# Battery_Monitor_5.net
KiCad netlist of a schematic drawn in EAGLE
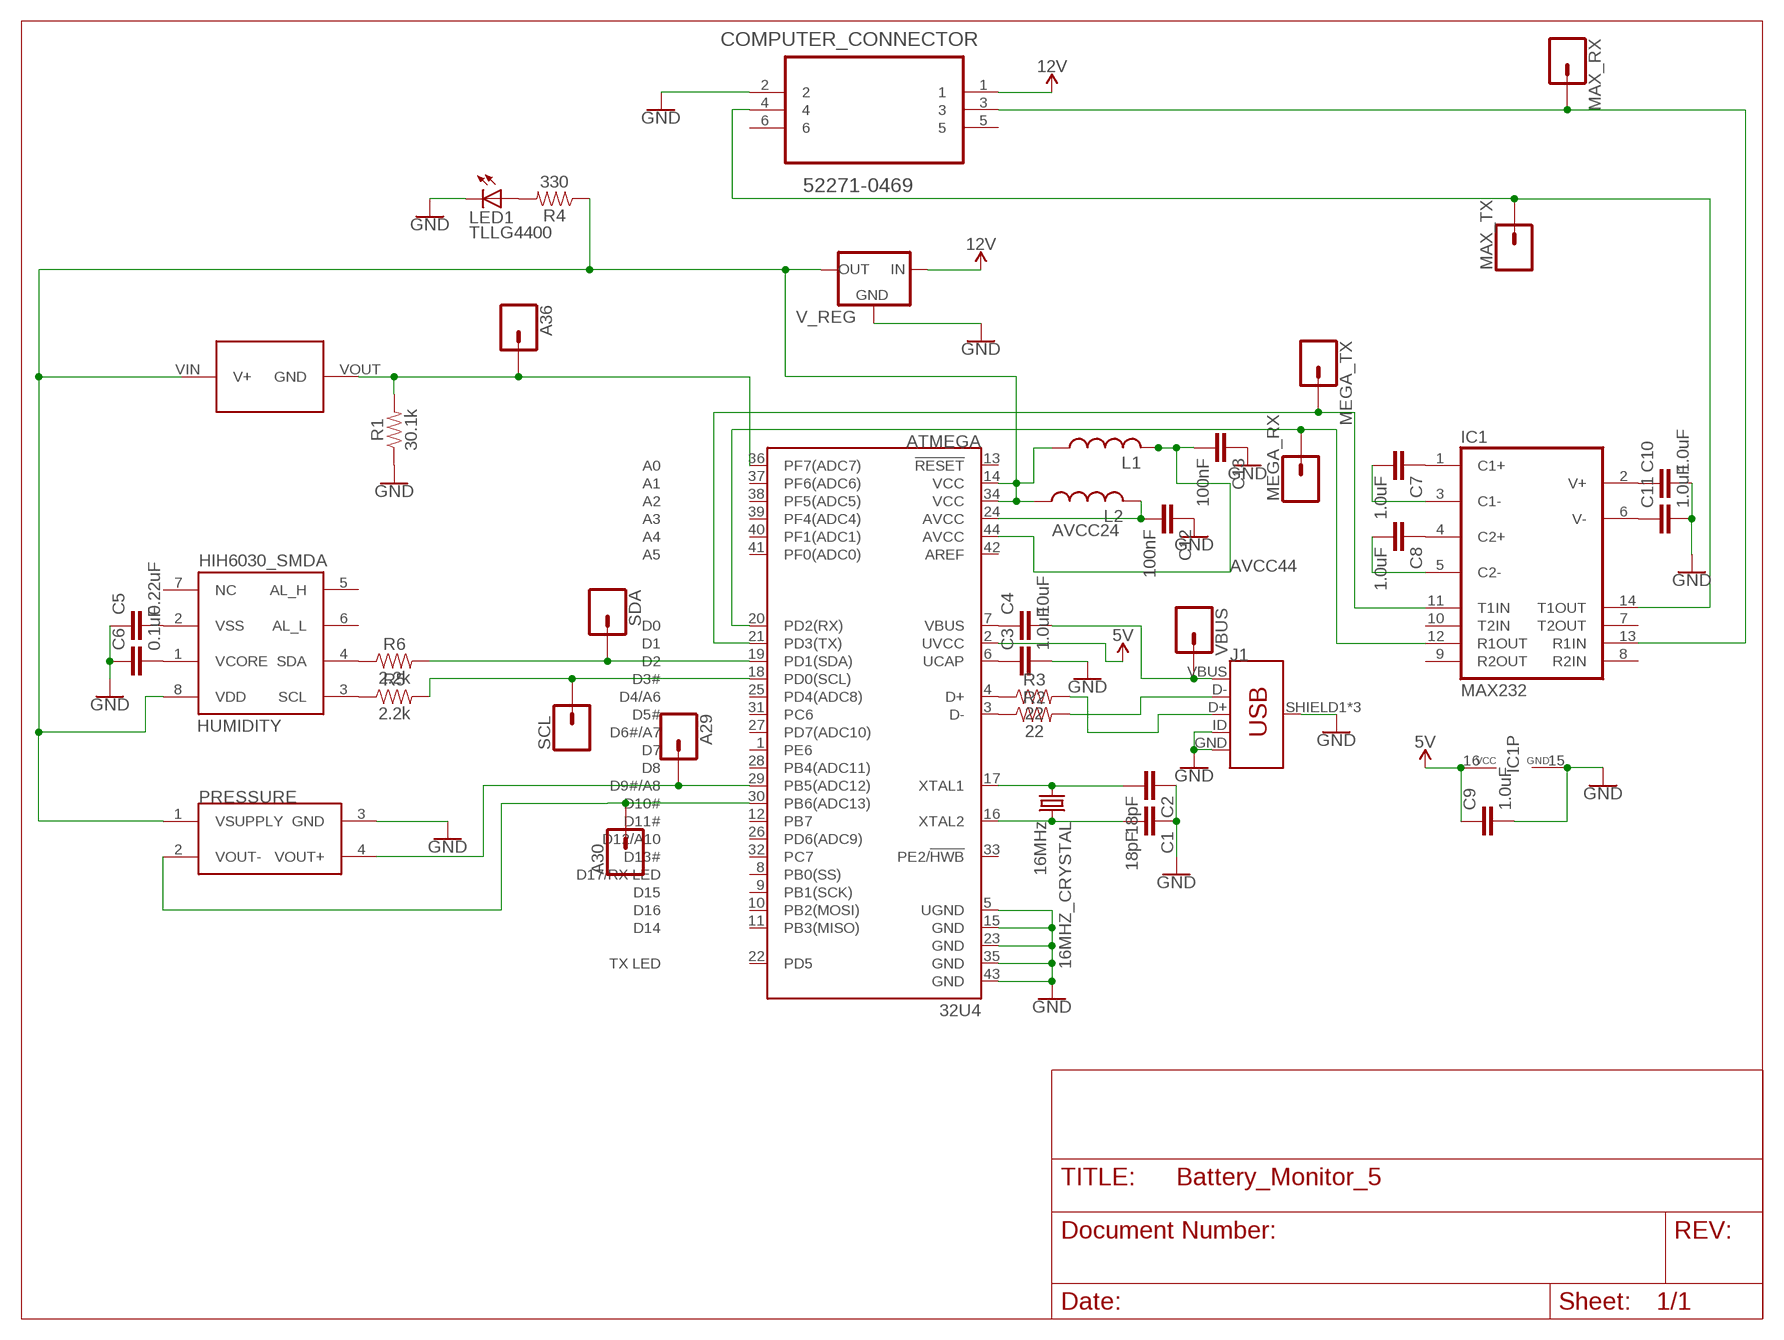
[diagram p0: schematic, sheet 1]

(export (version "E")
  (design (tool "Eeschema 10.0.6"))
  (components
    (comp (ref "16MHZ_CRYSTAL")
      (value "16MHz")
      (footprint "eagle-import:HC49_S")
      (libsource (lib "eagle-import") (part "CRYSTALHC49S"))
    )
    (comp (ref "A29")
      (value "CONN_01POGOPIN_HOLE_LARGE")
      (footprint "eagle-import:1X01_POGOPIN_HOLE_0.061_DIA")
      (libsource (lib "eagle-import") (part "CONN_01POGOPIN_HOLE_LARGE"))
    )
    (comp (ref "A30")
      (value "CONN_01POGOPIN_HOLE_LARGE")
      (footprint "eagle-import:1X01_POGOPIN_HOLE_0.061_DIA")
      (libsource (lib "eagle-import") (part "CONN_01POGOPIN_HOLE_LARGE"))
    )
    (comp (ref "A36")
      (value "CONN_01POGOPIN_HOLE_LARGE")
      (footprint "eagle-import:1X01_POGOPIN_HOLE_0.061_DIA")
      (libsource (lib "eagle-import") (part "CONN_01POGOPIN_HOLE_LARGE"))
    )
    (comp (ref "ATMEGA")
      (value "32U4")
      (footprint "eagle-import:QFN-44")
      (libsource (lib "eagle-import") (part "ATMEGA32U4QFN"))
    )
    (comp (ref "C1")
      (value "18pF")
      (footprint "eagle-import:0603")
      (libsource (lib "eagle-import") (part "18PF-0603-50V-5%"))
    )
    (comp (ref "C2")
      (value "18pF")
      (footprint "eagle-import:0603")
      (libsource (lib "eagle-import") (part "18PF-0603-50V-5%"))
    )
    (comp (ref "C3")
      (value "1.0uF")
      (footprint "eagle-import:0402")
      (libsource (lib "eagle-import") (part "1.0UF-0402-16V-10%"))
    )
    (comp (ref "C4")
      (value "10uF")
      (footprint "eagle-import:0603")
      (libsource (lib "eagle-import") (part "10UF-0603-6.3V-20%"))
    )
    (comp (ref "C5")
      (value "0.22uF")
      (footprint "eagle-import:0603")
      (libsource (lib "eagle-import") (part "0.22UF-0603-25V-10%"))
    )
    (comp (ref "C6")
      (value "0.1uF")
      (footprint "eagle-import:0402")
      (libsource (lib "eagle-import") (part "0.1UF-0402-16V-10%"))
    )
    (comp (ref "C7")
      (value "1.0uF")
      (footprint "eagle-import:0402")
      (libsource (lib "eagle-import") (part "1.0UF-0402-16V-10%"))
    )
    (comp (ref "C8")
      (value "1.0uF")
      (footprint "eagle-import:0402")
      (libsource (lib "eagle-import") (part "1.0UF-0402-16V-10%"))
    )
    (comp (ref "C9")
      (value "1.0uF")
      (footprint "eagle-import:0402")
      (libsource (lib "eagle-import") (part "1.0UF-0402-16V-10%"))
    )
    (comp (ref "C10")
      (value "1.0uF")
      (footprint "eagle-import:0402")
      (libsource (lib "eagle-import") (part "1.0UF-0402-16V-10%"))
    )
    (comp (ref "C11")
      (value "1.0uF")
      (footprint "eagle-import:0402")
      (libsource (lib "eagle-import") (part "1.0UF-0402-16V-10%"))
    )
    (comp (ref "C12")
      (value "100nF")
      (footprint "eagle-import:0402")
      (libsource (lib "eagle-import") (part "1.0UF-0402-16V-10%"))
    )
    (comp (ref "C13")
      (value "100nF")
      (footprint "eagle-import:0402")
      (libsource (lib "eagle-import") (part "1.0UF-0402-16V-10%"))
    )
    (comp (ref "COMPUTER_CONNECTOR")
      (value "52271-0469")
      (footprint "eagle-import:MOLEX_52271-0469")
      (libsource (lib "eagle-import") (part "52271-0469"))
    )
    (comp (ref "FLEX_SQ")
      (value "MOLEX_2WIRE2018")
      (footprint "eagle-import:SMT_MOLEX_PKG")
      (libsource (lib "eagle-import") (part "MOLEX_2WIRE2018"))
    )
    (comp (ref "HUMIDITY")
      (value "HIH6030_SMDA")
      (footprint "eagle-import:SMD-8")
      (libsource (lib "eagle-import") (part "HIH6030_SMDA"))
    )
    (comp (ref "IC1")
      (value "MAX232")
      (footprint "eagle-import:DIL16")
      (fields (field (name "MF") "MAXIM") (field (name "MPN") "MAX232ACPE+"))
      (libsource (lib "eagle-import") (part "MAX232"))
    )
    (comp (ref "J1")
      (value "USB_MICRO-B_FEMALE-SMT")
      (footprint "eagle-import:USB-B-MICRO-SMD")
      (libsource (lib "eagle-import") (part "USB_MICRO-B_FEMALE-SMT"))
    )
    (comp (ref "L1")
      (value "L-USL1812")
      (footprint "eagle-import:L1812")
      (libsource (lib "eagle-import") (part "L-USL1812"))
    )
    (comp (ref "L2")
      (value "L-USL1812")
      (footprint "eagle-import:L1812")
      (libsource (lib "eagle-import") (part "L-USL1812"))
    )
    (comp (ref "LED1")
      (value "TLLG4400")
      (footprint "eagle-import:LED3MM")
      (fields (field (name "MF") "VISHAY SEMICONDUCTOR"))
      (libsource (lib "eagle-import") (part "TLLG4400"))
    )
    (comp (ref "MAX_RX")
      (value "CONN_01POGOPIN_HOLE_LARGE")
      (footprint "eagle-import:1X01_POGOPIN_HOLE_0.061_DIA")
      (libsource (lib "eagle-import") (part "CONN_01POGOPIN_HOLE_LARGE"))
    )
    (comp (ref "MAX_TX")
      (value "CONN_01POGOPIN_HOLE_LARGE")
      (footprint "eagle-import:1X01_POGOPIN_HOLE_0.061_DIA")
      (libsource (lib "eagle-import") (part "CONN_01POGOPIN_HOLE_LARGE"))
    )
    (comp (ref "MEGA_RX")
      (value "CONN_01POGOPIN_HOLE_LARGE")
      (footprint "eagle-import:1X01_POGOPIN_HOLE_0.061_DIA")
      (libsource (lib "eagle-import") (part "CONN_01POGOPIN_HOLE_LARGE"))
    )
    (comp (ref "MEGA_TX")
      (value "CONN_01POGOPIN_HOLE_LARGE")
      (footprint "eagle-import:1X01_POGOPIN_HOLE_0.061_DIA")
      (libsource (lib "eagle-import") (part "CONN_01POGOPIN_HOLE_LARGE"))
    )
    (comp (ref "PRESSURE")
      (value "HONEYWELL_PRESSURE_SENSOR2018")
      (footprint "eagle-import:4PIN_SMT")
      (libsource (lib "eagle-import") (part "HONEYWELL_PRESSURE_SENSOR2018"))
    )
    (comp (ref "R1")
      (value "30.1k")
      (footprint "eagle-import:0603")
      (libsource (lib "eagle-import") (part "30.1KOHM-0603-1/10W-1%"))
    )
    (comp (ref "R2")
      (value "22")
      (footprint "eagle-import:0402")
      (libsource (lib "eagle-import") (part "22OHM-0402-1/10W-1%"))
    )
    (comp (ref "R3")
      (value "22")
      (footprint "eagle-import:0402")
      (libsource (lib "eagle-import") (part "22OHM-0402-1/10W-1%"))
    )
    (comp (ref "R4")
      (value "330")
      (footprint "eagle-import:0603")
      (libsource (lib "eagle-import") (part "330OHM-0603-1/10W-1%"))
    )
    (comp (ref "R5")
      (value "2.2k")
      (footprint "eagle-import:0603")
      (libsource (lib "eagle-import") (part "2.2KOHM-0603-1/10W-1%"))
    )
    (comp (ref "R6")
      (value "2.2k")
      (footprint "eagle-import:0603")
      (libsource (lib "eagle-import") (part "2.2KOHM-0603-1/10W-1%"))
    )
    (comp (ref "SCL")
      (value "CONN_01POGOPIN_HOLE_LARGE")
      (footprint "eagle-import:1X01_POGOPIN_HOLE_0.061_DIA")
      (libsource (lib "eagle-import") (part "CONN_01POGOPIN_HOLE_LARGE"))
    )
    (comp (ref "SDA")
      (value "CONN_01POGOPIN_HOLE_LARGE")
      (footprint "eagle-import:1X01_POGOPIN_HOLE_0.061_DIA")
      (libsource (lib "eagle-import") (part "CONN_01POGOPIN_HOLE_LARGE"))
    )
    (comp (ref "VBUS")
      (value "CONN_01POGOPIN_HOLE_LARGE")
      (footprint "eagle-import:1X01_POGOPIN_HOLE_0.061_DIA")
      (libsource (lib "eagle-import") (part "CONN_01POGOPIN_HOLE_LARGE"))
    )
    (comp (ref "V_REG")
      (value "DC_DC_78XXA")
      (footprint "eagle-import:DC-DC_CONVERTER_78XX")
      (libsource (lib "eagle-import") (part "DC_DC_78XXA"))
    )
  )
  (nets
    (net (code "1") (name "/AVCC24") (class "Default")
      (node (ref "ATMEGA") (pin "24") (pinfunction "AVCC_24") (pintype "bidirectional"))
      (node (ref "C12") (pin "2") (pinfunction "2_2") (pintype "passive"))
      (node (ref "L2") (pin "2") (pinfunction "2_2") (pintype "passive"))
    )
    (net (code "2") (name "/AVCC44") (class "Default")
      (node (ref "ATMEGA") (pin "44") (pinfunction "AVCC_44") (pintype "bidirectional"))
      (node (ref "C13") (pin "2") (pinfunction "2_2") (pintype "passive"))
      (node (ref "L1") (pin "2") (pinfunction "2_2") (pintype "passive"))
    )
    (net (code "3") (name "5V") (class "Default")
      (node (ref "ATMEGA") (pin "14") (pinfunction "VCC_14") (pintype "bidirectional"))
      (node (ref "ATMEGA") (pin "2") (pinfunction "UVCC_2") (pintype "bidirectional"))
      (node (ref "ATMEGA") (pin "34") (pinfunction "VCC_34") (pintype "bidirectional"))
      (node (ref "C9") (pin "1") (pinfunction "1_1") (pintype "passive"))
      (node (ref "FLEX_SQ") (pin "VIN") (pinfunction "V+_VIN") (pintype "bidirectional"))
      (node (ref "HUMIDITY") (pin "8") (pinfunction "VDD_8") (pintype "bidirectional"))
      (node (ref "IC1") (pin "16") (pinfunction "VCC_16") (pintype "power_in"))
      (node (ref "L1") (pin "1") (pinfunction "1_1") (pintype "passive"))
      (node (ref "L2") (pin "1") (pinfunction "1_1") (pintype "passive"))
      (node (ref "PRESSURE") (pin "1") (pinfunction "VSUPPLY_1") (pintype "bidirectional"))
      (node (ref "R4") (pin "1") (pinfunction "1_1") (pintype "passive"))
      (node (ref "V_REG") (pin "VOUT") (pinfunction "OUT_VOUT") (pintype "passive"))
    )
    (net (code "4") (name "12V") (class "Default")
      (node (ref "COMPUTER_CONNECTOR") (pin "1") (pinfunction "1_1") (pintype "passive"))
      (node (ref "V_REG") (pin "VIN") (pinfunction "IN_VIN") (pintype "input"))
    )
    (net (code "5") (name "GND") (class "Default")
      (node (ref "ATMEGA") (pin "15") (pinfunction "GND_15") (pintype "bidirectional"))
      (node (ref "ATMEGA") (pin "23") (pinfunction "GND_23") (pintype "bidirectional"))
      (node (ref "ATMEGA") (pin "35") (pinfunction "GND_35") (pintype "bidirectional"))
      (node (ref "ATMEGA") (pin "43") (pinfunction "GND_43") (pintype "bidirectional"))
      (node (ref "ATMEGA") (pin "5") (pinfunction "UGND_5") (pintype "bidirectional"))
      (node (ref "C1") (pin "1") (pinfunction "1_1") (pintype "passive"))
      (node (ref "C10") (pin "2") (pinfunction "2_2") (pintype "passive"))
      (node (ref "C11") (pin "2") (pinfunction "2_2") (pintype "passive"))
      (node (ref "C12") (pin "1") (pinfunction "1_1") (pintype "passive"))
      (node (ref "C13") (pin "1") (pinfunction "1_1") (pintype "passive"))
      (node (ref "C2") (pin "1") (pinfunction "1_1") (pintype "passive"))
      (node (ref "C3") (pin "2") (pinfunction "2_2") (pintype "passive"))
      (node (ref "C5") (pin "1") (pinfunction "1_1") (pintype "passive"))
      (node (ref "C6") (pin "1") (pinfunction "1_1") (pintype "passive"))
      (node (ref "C9") (pin "2") (pinfunction "2_2") (pintype "passive"))
      (node (ref "COMPUTER_CONNECTOR") (pin "2") (pinfunction "2_2") (pintype "passive"))
      (node (ref "IC1") (pin "15") (pinfunction "GND_15") (pintype "power_in"))
      (node (ref "J1") (pin "GND") (pinfunction "GND_GND") (pintype "power_in"))
      (node (ref "J1") (pin "ID") (pinfunction "ID_ID") (pintype "bidirectional"))
      (node (ref "J1") (pin "SHIELD1") (pinfunction "SHIELD_SHIELD1") (pintype "bidirectional"))
      (node (ref "J1") (pin "SHIELD2") (pinfunction "SHIELD_SHIELD2") (pintype "bidirectional"))
      (node (ref "J1") (pin "SHIELD3") (pinfunction "SHIELD_SHIELD3") (pintype "bidirectional"))
      (node (ref "LED1") (pin "K") (pinfunction "C_K") (pintype "passive"))
      (node (ref "PRESSURE") (pin "3") (pinfunction "GND_3") (pintype "bidirectional"))
      (node (ref "R1") (pin "1") (pinfunction "1_1") (pintype "passive"))
      (node (ref "V_REG") (pin "GND") (pinfunction "GND_GND") (pintype "input"))
    )
    (net (code "6") (name "Net-(ATMEGA-D+)") (class "Default")
      (node (ref "ATMEGA") (pin "4") (pinfunction "D+_4") (pintype "bidirectional"))
      (node (ref "R3") (pin "1") (pinfunction "1_1") (pintype "passive"))
    )
    (net (code "7") (name "Net-(ATMEGA-D-)") (class "Default")
      (node (ref "ATMEGA") (pin "3") (pinfunction "D-_3") (pintype "bidirectional"))
      (node (ref "R2") (pin "1") (pinfunction "1_1") (pintype "passive"))
    )
    (net (code "8") (name "Net-(ATMEGA-PB5(ADC12))") (class "Default")
      (node (ref "A29") (pin "1") (pinfunction "1_1") (pintype "passive"))
      (node (ref "ATMEGA") (pin "29") (pinfunction "PB5(ADC12)_29") (pintype "bidirectional"))
      (node (ref "PRESSURE") (pin "4") (pinfunction "VOUT+_4") (pintype "bidirectional"))
    )
    (net (code "9") (name "Net-(ATMEGA-PB6(ADC13))") (class "Default")
      (node (ref "A30") (pin "1") (pinfunction "1_1") (pintype "passive"))
      (node (ref "ATMEGA") (pin "30") (pinfunction "PB6(ADC13)_30") (pintype "bidirectional"))
      (node (ref "PRESSURE") (pin "2") (pinfunction "VOUT-_2") (pintype "bidirectional"))
    )
    (net (code "10") (name "Net-(ATMEGA-PD0(SCL))") (class "Default")
      (node (ref "ATMEGA") (pin "18") (pinfunction "PD0(SCL)_18") (pintype "bidirectional"))
      (node (ref "R5") (pin "2") (pinfunction "2_2") (pintype "passive"))
      (node (ref "SCL") (pin "1") (pinfunction "1_1") (pintype "passive"))
    )
    (net (code "11") (name "Net-(ATMEGA-PD1(SDA))") (class "Default")
      (node (ref "ATMEGA") (pin "19") (pinfunction "PD1(SDA)_19") (pintype "bidirectional"))
      (node (ref "R6") (pin "2") (pinfunction "2_2") (pintype "passive"))
      (node (ref "SDA") (pin "1") (pinfunction "1_1") (pintype "passive"))
    )
    (net (code "12") (name "Net-(ATMEGA-PD2(RX))") (class "Default")
      (node (ref "ATMEGA") (pin "20") (pinfunction "PD2(RX)_20") (pintype "bidirectional"))
      (node (ref "IC1") (pin "12") (pinfunction "R1OUT_12") (pintype "output"))
      (node (ref "MEGA_RX") (pin "1") (pinfunction "1_1") (pintype "passive"))
    )
    (net (code "13") (name "Net-(ATMEGA-PD3(TX))") (class "Default")
      (node (ref "ATMEGA") (pin "21") (pinfunction "PD3(TX)_21") (pintype "bidirectional"))
      (node (ref "IC1") (pin "11") (pinfunction "T1IN_11") (pintype "input"))
      (node (ref "MEGA_TX") (pin "1") (pinfunction "1_1") (pintype "passive"))
    )
    (net (code "14") (name "Net-(ATMEGA-PF7(ADC7))") (class "Default")
      (node (ref "A36") (pin "1") (pinfunction "1_1") (pintype "passive"))
      (node (ref "ATMEGA") (pin "36") (pinfunction "PF7(ADC7)_36") (pintype "bidirectional"))
      (node (ref "FLEX_SQ") (pin "VOUT") (pinfunction "GND_VOUT") (pintype "bidirectional"))
      (node (ref "R1") (pin "2") (pinfunction "2_2") (pintype "passive"))
    )
    (net (code "15") (name "Net-(ATMEGA-UCAP)") (class "Default")
      (node (ref "ATMEGA") (pin "6") (pinfunction "UCAP_6") (pintype "bidirectional"))
      (node (ref "C3") (pin "1") (pinfunction "1_1") (pintype "passive"))
    )
    (net (code "16") (name "Net-(ATMEGA-VBUS)") (class "Default")
      (node (ref "ATMEGA") (pin "7") (pinfunction "VBUS_7") (pintype "bidirectional"))
      (node (ref "C4") (pin "1") (pinfunction "1_1") (pintype "passive"))
    )
    (net (code "17") (name "Net-(ATMEGA-XTAL1)") (class "Default")
      (node (ref "16MHZ_CRYSTAL") (pin "1") (pinfunction "1_1") (pintype "passive"))
      (node (ref "ATMEGA") (pin "17") (pinfunction "XTAL1_17") (pintype "bidirectional"))
      (node (ref "C2") (pin "2") (pinfunction "2_2") (pintype "passive"))
    )
    (net (code "18") (name "Net-(ATMEGA-XTAL2)") (class "Default")
      (node (ref "16MHZ_CRYSTAL") (pin "2") (pinfunction "2_2") (pintype "passive"))
      (node (ref "ATMEGA") (pin "16") (pinfunction "XTAL2_16") (pintype "bidirectional"))
      (node (ref "C1") (pin "2") (pinfunction "2_2") (pintype "passive"))
    )
    (net (code "19") (name "Net-(C4-Pad2)") (class "Default")
      (node (ref "C4") (pin "2") (pinfunction "2_2") (pintype "passive"))
      (node (ref "J1") (pin "VBUS") (pinfunction "VBUS_VBUS") (pintype "power_in"))
      (node (ref "VBUS") (pin "1") (pinfunction "1_1") (pintype "passive"))
    )
    (net (code "20") (name "Net-(HUMIDITY-SCL)") (class "Default")
      (node (ref "HUMIDITY") (pin "3") (pinfunction "SCL_3") (pintype "bidirectional"))
      (node (ref "R5") (pin "1") (pinfunction "1_1") (pintype "passive"))
    )
    (net (code "21") (name "Net-(HUMIDITY-SDA)") (class "Default")
      (node (ref "HUMIDITY") (pin "4") (pinfunction "SDA_4") (pintype "bidirectional"))
      (node (ref "R6") (pin "1") (pinfunction "1_1") (pintype "passive"))
    )
    (net (code "22") (name "Net-(HUMIDITY-VCORE)") (class "Default")
      (node (ref "C6") (pin "2") (pinfunction "2_2") (pintype "passive"))
      (node (ref "HUMIDITY") (pin "1") (pinfunction "VCORE_1") (pintype "bidirectional"))
    )
    (net (code "23") (name "Net-(HUMIDITY-VSS)") (class "Default")
      (node (ref "C5") (pin "2") (pinfunction "2_2") (pintype "passive"))
      (node (ref "HUMIDITY") (pin "2") (pinfunction "VSS_2") (pintype "bidirectional"))
    )
    (net (code "24") (name "Net-(IC1A-C1+)") (class "Default")
      (node (ref "C7") (pin "1") (pinfunction "1_1") (pintype "passive"))
      (node (ref "IC1") (pin "1") (pinfunction "C1+_1") (pintype "bidirectional"))
    )
    (net (code "25") (name "Net-(IC1A-C1-)") (class "Default")
      (node (ref "C7") (pin "2") (pinfunction "2_2") (pintype "passive"))
      (node (ref "IC1") (pin "3") (pinfunction "C1-_3") (pintype "bidirectional"))
    )
    (net (code "26") (name "Net-(IC1A-C2+)") (class "Default")
      (node (ref "C8") (pin "1") (pinfunction "1_1") (pintype "passive"))
      (node (ref "IC1") (pin "4") (pinfunction "C2+_4") (pintype "bidirectional"))
    )
    (net (code "27") (name "Net-(IC1A-C2-)") (class "Default")
      (node (ref "C8") (pin "2") (pinfunction "2_2") (pintype "passive"))
      (node (ref "IC1") (pin "5") (pinfunction "C2-_5") (pintype "bidirectional"))
    )
    (net (code "28") (name "Net-(IC1A-R1IN)") (class "Default")
      (node (ref "COMPUTER_CONNECTOR") (pin "3") (pinfunction "3_3") (pintype "passive"))
      (node (ref "IC1") (pin "13") (pinfunction "R1IN_13") (pintype "input"))
      (node (ref "MAX_RX") (pin "1") (pinfunction "1_1") (pintype "passive"))
    )
    (net (code "29") (name "Net-(IC1A-T1OUT)") (class "Default")
      (node (ref "COMPUTER_CONNECTOR") (pin "4") (pinfunction "4_4") (pintype "passive"))
      (node (ref "IC1") (pin "14") (pinfunction "T1OUT_14") (pintype "output"))
      (node (ref "MAX_TX") (pin "1") (pinfunction "1_1") (pintype "passive"))
    )
    (net (code "30") (name "Net-(IC1A-V+)") (class "Default")
      (node (ref "C10") (pin "1") (pinfunction "1_1") (pintype "passive"))
      (node (ref "IC1") (pin "2") (pinfunction "V+_2") (pintype "bidirectional"))
    )
    (net (code "31") (name "Net-(IC1A-V-)") (class "Default")
      (node (ref "C11") (pin "1") (pinfunction "1_1") (pintype "passive"))
      (node (ref "IC1") (pin "6") (pinfunction "V-_6") (pintype "bidirectional"))
    )
    (net (code "32") (name "Net-(J1-PadD+)") (class "Default")
      (node (ref "J1") (pin "D+") (pinfunction "D+_D+") (pintype "bidirectional"))
      (node (ref "R3") (pin "2") (pinfunction "2_2") (pintype "passive"))
    )
    (net (code "33") (name "Net-(J1-PadD-)") (class "Default")
      (node (ref "J1") (pin "D-") (pinfunction "D-_D-") (pintype "bidirectional"))
      (node (ref "R2") (pin "2") (pinfunction "2_2") (pintype "passive"))
    )
    (net (code "34") (name "Net-(LED1-PadA)") (class "Default")
      (node (ref "LED1") (pin "A") (pinfunction "A_A") (pintype "passive"))
      (node (ref "R4") (pin "2") (pinfunction "2_2") (pintype "passive"))
    )
    (net (code "35") (name "unconnected-(ATMEGA-AREF-Pad42)") (class "Default")
      (node (ref "ATMEGA") (pin "42") (pinfunction "AREF_42") (pintype "bidirectional"))
    )
    (net (code "36") (name "unconnected-(ATMEGA-PB0(SS)-Pad8)") (class "Default")
      (node (ref "ATMEGA") (pin "8") (pinfunction "PB0(SS)_8") (pintype "bidirectional"))
    )
    (net (code "37") (name "unconnected-(ATMEGA-PB1(SCK)-Pad9)") (class "Default")
      (node (ref "ATMEGA") (pin "9") (pinfunction "PB1(SCK)_9") (pintype "bidirectional"))
    )
    (net (code "38") (name "unconnected-(ATMEGA-PB2(MOSI)-Pad10)") (class "Default")
      (node (ref "ATMEGA") (pin "10") (pinfunction "PB2(MOSI)_10") (pintype "bidirectional"))
    )
    (net (code "39") (name "unconnected-(ATMEGA-PB3(MISO)-Pad11)") (class "Default")
      (node (ref "ATMEGA") (pin "11") (pinfunction "PB3(MISO)_11") (pintype "bidirectional"))
    )
    (net (code "40") (name "unconnected-(ATMEGA-PB4(ADC11)-Pad28)") (class "Default")
      (node (ref "ATMEGA") (pin "28") (pinfunction "PB4(ADC11)_28") (pintype "bidirectional"))
    )
    (net (code "41") (name "unconnected-(ATMEGA-PB7-Pad12)") (class "Default")
      (node (ref "ATMEGA") (pin "12") (pinfunction "PB7_12") (pintype "bidirectional"))
    )
    (net (code "42") (name "unconnected-(ATMEGA-PC6-Pad31)") (class "Default")
      (node (ref "ATMEGA") (pin "31") (pinfunction "PC6_31") (pintype "bidirectional"))
    )
    (net (code "43") (name "unconnected-(ATMEGA-PC7-Pad32)") (class "Default")
      (node (ref "ATMEGA") (pin "32") (pinfunction "PC7_32") (pintype "bidirectional"))
    )
    (net (code "44") (name "unconnected-(ATMEGA-PD4(ADC8)-Pad25)") (class "Default")
      (node (ref "ATMEGA") (pin "25") (pinfunction "PD4(ADC8)_25") (pintype "bidirectional"))
    )
    (net (code "45") (name "unconnected-(ATMEGA-PD5-Pad22)") (class "Default")
      (node (ref "ATMEGA") (pin "22") (pinfunction "PD5_22") (pintype "bidirectional"))
    )
    (net (code "46") (name "unconnected-(ATMEGA-PD6(ADC9)-Pad26)") (class "Default")
      (node (ref "ATMEGA") (pin "26") (pinfunction "PD6(ADC9)_26") (pintype "bidirectional"))
    )
    (net (code "47") (name "unconnected-(ATMEGA-PD7(ADC10)-Pad27)") (class "Default")
      (node (ref "ATMEGA") (pin "27") (pinfunction "PD7(ADC10)_27") (pintype "bidirectional"))
    )
    (net (code "48") (name "unconnected-(ATMEGA-PE2{slash}~{HWB}-Pad33)") (class "Default")
      (node (ref "ATMEGA") (pin "33") (pinfunction "PE2/~{HWB}_33") (pintype "bidirectional"))
    )
    (net (code "49") (name "unconnected-(ATMEGA-PE6-Pad1)") (class "Default")
      (node (ref "ATMEGA") (pin "1") (pinfunction "PE6_1") (pintype "bidirectional"))
    )
    (net (code "50") (name "unconnected-(ATMEGA-PF0(ADC0)-Pad41)") (class "Default")
      (node (ref "ATMEGA") (pin "41") (pinfunction "PF0(ADC0)_41") (pintype "bidirectional"))
    )
    (net (code "51") (name "unconnected-(ATMEGA-PF1(ADC1)-Pad40)") (class "Default")
      (node (ref "ATMEGA") (pin "40") (pinfunction "PF1(ADC1)_40") (pintype "bidirectional"))
    )
    (net (code "52") (name "unconnected-(ATMEGA-PF4(ADC4)-Pad39)") (class "Default")
      (node (ref "ATMEGA") (pin "39") (pinfunction "PF4(ADC4)_39") (pintype "bidirectional"))
    )
    (net (code "53") (name "unconnected-(ATMEGA-PF5(ADC5)-Pad38)") (class "Default")
      (node (ref "ATMEGA") (pin "38") (pinfunction "PF5(ADC5)_38") (pintype "bidirectional"))
    )
    (net (code "54") (name "unconnected-(ATMEGA-PF6(ADC6)-Pad37)") (class "Default")
      (node (ref "ATMEGA") (pin "37") (pinfunction "PF6(ADC6)_37") (pintype "bidirectional"))
    )
    (net (code "55") (name "unconnected-(ATMEGA-~{RESET}-Pad13)") (class "Default")
      (node (ref "ATMEGA") (pin "13") (pinfunction "~{RESET}_13") (pintype "bidirectional"))
    )
    (net (code "56") (name "unconnected-(COMPUTER_CONNECTOR-Pad5)") (class "Default")
      (node (ref "COMPUTER_CONNECTOR") (pin "5") (pinfunction "5_5") (pintype "passive"))
    )
    (net (code "57") (name "unconnected-(COMPUTER_CONNECTOR-Pad6)") (class "Default")
      (node (ref "COMPUTER_CONNECTOR") (pin "6") (pinfunction "6_6") (pintype "passive"))
    )
    (net (code "58") (name "unconnected-(HUMIDITY-AL_H-Pad5)") (class "Default")
      (node (ref "HUMIDITY") (pin "5") (pinfunction "AL_H_5") (pintype "bidirectional"))
    )
    (net (code "59") (name "unconnected-(HUMIDITY-AL_L-Pad6)") (class "Default")
      (node (ref "HUMIDITY") (pin "6") (pinfunction "AL_L_6") (pintype "bidirectional"))
    )
    (net (code "60") (name "unconnected-(HUMIDITY-NC-Pad7)") (class "Default")
      (node (ref "HUMIDITY") (pin "7") (pinfunction "NC_7") (pintype "bidirectional"))
    )
    (net (code "61") (name "unconnected-(IC1A-R2IN-Pad8)") (class "Default")
      (node (ref "IC1") (pin "8") (pinfunction "R2IN_8") (pintype "input"))
    )
    (net (code "62") (name "unconnected-(IC1A-R2OUT-Pad9)") (class "Default")
      (node (ref "IC1") (pin "9") (pinfunction "R2OUT_9") (pintype "output"))
    )
    (net (code "63") (name "unconnected-(IC1A-T2IN-Pad10)") (class "Default")
      (node (ref "IC1") (pin "10") (pinfunction "T2IN_10") (pintype "input"))
    )
    (net (code "64") (name "unconnected-(IC1A-T2OUT-Pad7)") (class "Default")
      (node (ref "IC1") (pin "7") (pinfunction "T2OUT_7") (pintype "output"))
    )
  )
)
